# Macropadmod.net
KiCad netlist of a schematic drawn in Altium Designer
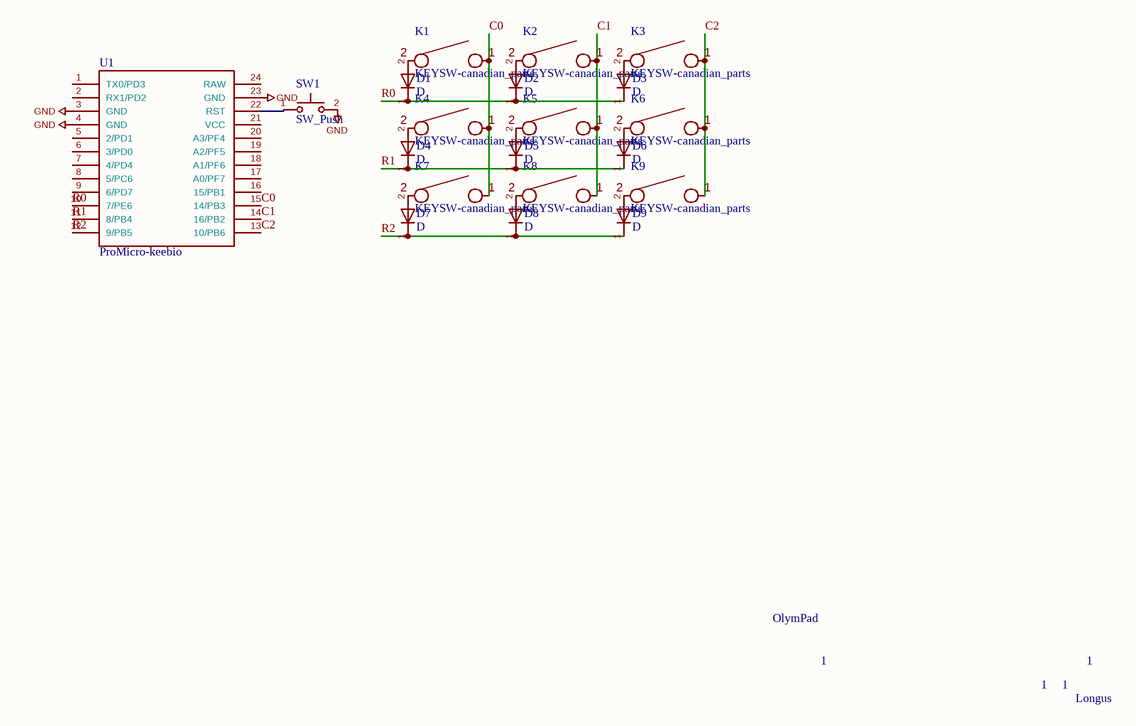
[diagram p0: Macropadmod.SchDoc]

(export (version "E")
  (design (tool "Eeschema 10.0.6"))
  (components
    (comp (ref "D1") (value "D") (footprint "Diode") (libsource (lib "Macropad") (part "D")))
    (comp (ref "D2") (value "D") (footprint "Diode") (libsource (lib "Macropad") (part "D")))
    (comp (ref "D3") (value "D") (footprint "Diode") (libsource (lib "Macropad") (part "D")))
    (comp (ref "D4") (value "D") (footprint "Diode") (libsource (lib "Macropad") (part "D")))
    (comp (ref "D5") (value "D") (footprint "Diode") (libsource (lib "Macropad") (part "D")))
    (comp (ref "D6") (value "D") (footprint "Diode") (libsource (lib "Macropad") (part "D")))
    (comp (ref "D7") (value "D") (footprint "Diode") (libsource (lib "Macropad") (part "D")))
    (comp (ref "D8") (value "D") (footprint "Diode") (libsource (lib "Macropad") (part "D")))
    (comp (ref "D9") (value "D") (footprint "Diode") (libsource (lib "Macropad") (part "D")))
    (comp (ref "K1")
      (value "KEYSW-canadian_parts")
      (footprint "Socket")
      (libsource (lib "Macropad") (part "KEYSW-canadian_parts"))
    )
    (comp (ref "K2")
      (value "KEYSW-canadian_parts")
      (footprint "Socket")
      (libsource (lib "Macropad") (part "KEYSW-canadian_parts"))
    )
    (comp (ref "K3")
      (value "KEYSW-canadian_parts")
      (footprint "Socket")
      (libsource (lib "Macropad") (part "KEYSW-canadian_parts"))
    )
    (comp (ref "K4")
      (value "KEYSW-canadian_parts")
      (footprint "Socket")
      (libsource (lib "Macropad") (part "KEYSW-canadian_parts"))
    )
    (comp (ref "K5")
      (value "KEYSW-canadian_parts")
      (footprint "Socket")
      (libsource (lib "Macropad") (part "KEYSW-canadian_parts"))
    )
    (comp (ref "K6")
      (value "KEYSW-canadian_parts")
      (footprint "Socket")
      (libsource (lib "Macropad") (part "KEYSW-canadian_parts"))
    )
    (comp (ref "K7")
      (value "KEYSW-canadian_parts")
      (footprint "Socket")
      (libsource (lib "Macropad") (part "KEYSW-canadian_parts"))
    )
    (comp (ref "K8")
      (value "KEYSW-canadian_parts")
      (footprint "Socket")
      (libsource (lib "Macropad") (part "KEYSW-canadian_parts"))
    )
    (comp (ref "K9")
      (value "KEYSW-canadian_parts")
      (footprint "Socket")
      (libsource (lib "Macropad") (part "KEYSW-canadian_parts"))
    )
    (comp (ref "SW1") (value "SW_Push") (footprint "Reset") (libsource (lib "Macropad") (part "SW_Push")))
    (comp (ref "U1")
      (value "ProMicro-keebio")
      (footprint "Pro-Micro")
      (libsource (lib "Macropad") (part "ProMicro-keebio"))
    )
  )
  (nets
    (net (code "1") (name "/C0") (class "Default")
      (node (ref "K1") (pin "1") (pinfunction "1_1") (pintype "passive"))
      (node (ref "K4") (pin "1") (pinfunction "1_1") (pintype "passive"))
      (node (ref "K7") (pin "1") (pinfunction "1_1") (pintype "passive"))
      (node (ref "U1") (pin "15") (pinfunction "14/PB3_15") (pintype "passive"))
    )
    (net (code "2") (name "/C1") (class "Default")
      (node (ref "K2") (pin "1") (pinfunction "1_1") (pintype "passive"))
      (node (ref "K5") (pin "1") (pinfunction "1_1") (pintype "passive"))
      (node (ref "K8") (pin "1") (pinfunction "1_1") (pintype "passive"))
      (node (ref "U1") (pin "14") (pinfunction "16/PB2_14") (pintype "passive"))
    )
    (net (code "3") (name "/C2") (class "Default")
      (node (ref "K3") (pin "1") (pinfunction "1_1") (pintype "passive"))
      (node (ref "K6") (pin "1") (pinfunction "1_1") (pintype "passive"))
      (node (ref "K9") (pin "1") (pinfunction "1_1") (pintype "passive"))
      (node (ref "U1") (pin "13") (pinfunction "10/PB6_13") (pintype "passive"))
    )
    (net (code "4") (name "/R0") (class "Default")
      (node (ref "D1") (pin "1") (pinfunction "K_1") (pintype "passive"))
      (node (ref "D2") (pin "1") (pinfunction "K_1") (pintype "passive"))
      (node (ref "D3") (pin "1") (pinfunction "K_1") (pintype "passive"))
      (node (ref "U1") (pin "10") (pinfunction "7/PE6_10") (pintype "passive"))
    )
    (net (code "5") (name "/R1") (class "Default")
      (node (ref "D4") (pin "1") (pinfunction "K_1") (pintype "passive"))
      (node (ref "D5") (pin "1") (pinfunction "K_1") (pintype "passive"))
      (node (ref "D6") (pin "1") (pinfunction "K_1") (pintype "passive"))
      (node (ref "U1") (pin "11") (pinfunction "8/PB4_11") (pintype "passive"))
    )
    (net (code "6") (name "/R2") (class "Default")
      (node (ref "D7") (pin "1") (pinfunction "K_1") (pintype "passive"))
      (node (ref "D8") (pin "1") (pinfunction "K_1") (pintype "passive"))
      (node (ref "D9") (pin "1") (pinfunction "K_1") (pintype "passive"))
      (node (ref "U1") (pin "12") (pinfunction "9/PB5_12") (pintype "passive"))
    )
    (net (code "7") (name "GND") (class "Default")
      (node (ref "SW1") (pin "2") (pinfunction "2_2") (pintype "passive"))
      (node (ref "U1") (pin "23") (pinfunction "GND_23") (pintype "passive"))
      (node (ref "U1") (pin "3") (pinfunction "GND_3") (pintype "passive"))
      (node (ref "U1") (pin "4") (pinfunction "GND_4") (pintype "passive"))
    )
    (net (code "8") (name "Net-(D1-A)") (class "Default")
      (node (ref "D1") (pin "2") (pinfunction "A_2") (pintype "passive"))
      (node (ref "K1") (pin "2") (pinfunction "2_2") (pintype "passive"))
    )
    (net (code "9") (name "Net-(D2-A)") (class "Default")
      (node (ref "D2") (pin "2") (pinfunction "A_2") (pintype "passive"))
      (node (ref "K2") (pin "2") (pinfunction "2_2") (pintype "passive"))
    )
    (net (code "10") (name "Net-(D3-A)") (class "Default")
      (node (ref "D3") (pin "2") (pinfunction "A_2") (pintype "passive"))
      (node (ref "K3") (pin "2") (pinfunction "2_2") (pintype "passive"))
    )
    (net (code "11") (name "Net-(D4-A)") (class "Default")
      (node (ref "D4") (pin "2") (pinfunction "A_2") (pintype "passive"))
      (node (ref "K4") (pin "2") (pinfunction "2_2") (pintype "passive"))
    )
    (net (code "12") (name "Net-(D5-A)") (class "Default")
      (node (ref "D5") (pin "2") (pinfunction "A_2") (pintype "passive"))
      (node (ref "K5") (pin "2") (pinfunction "2_2") (pintype "passive"))
    )
    (net (code "13") (name "Net-(D6-A)") (class "Default")
      (node (ref "D6") (pin "2") (pinfunction "A_2") (pintype "passive"))
      (node (ref "K6") (pin "2") (pinfunction "2_2") (pintype "passive"))
    )
    (net (code "14") (name "Net-(D7-A)") (class "Default")
      (node (ref "D7") (pin "2") (pinfunction "A_2") (pintype "passive"))
      (node (ref "K7") (pin "2") (pinfunction "2_2") (pintype "passive"))
    )
    (net (code "15") (name "Net-(D8-A)") (class "Default")
      (node (ref "D8") (pin "2") (pinfunction "A_2") (pintype "passive"))
      (node (ref "K8") (pin "2") (pinfunction "2_2") (pintype "passive"))
    )
    (net (code "16") (name "Net-(D9-A)") (class "Default")
      (node (ref "D9") (pin "2") (pinfunction "A_2") (pintype "passive"))
      (node (ref "K9") (pin "2") (pinfunction "2_2") (pintype "passive"))
    )
    (net (code "17") (name "Net-(U1-RST)") (class "Default")
      (node (ref "SW1") (pin "1") (pinfunction "1_1") (pintype "passive"))
      (node (ref "U1") (pin "22") (pinfunction "RST_22") (pintype "passive"))
    )
    (net (code "18") (name "unconnected-(U1-2{slash}PD1-Pad5)") (class "Default")
      (node (ref "U1") (pin "5") (pinfunction "2/PD1_5") (pintype "passive"))
    )
    (net (code "19") (name "unconnected-(U1-3{slash}PD0-Pad6)") (class "Default")
      (node (ref "U1") (pin "6") (pinfunction "3/PD0_6") (pintype "passive"))
    )
    (net (code "20") (name "unconnected-(U1-4{slash}PD4-Pad7)") (class "Default")
      (node (ref "U1") (pin "7") (pinfunction "4/PD4_7") (pintype "passive"))
    )
    (net (code "21") (name "unconnected-(U1-5{slash}PC6-Pad8)") (class "Default")
      (node (ref "U1") (pin "8") (pinfunction "5/PC6_8") (pintype "passive"))
    )
    (net (code "22") (name "unconnected-(U1-6{slash}PD7-Pad9)") (class "Default")
      (node (ref "U1") (pin "9") (pinfunction "6/PD7_9") (pintype "passive"))
    )
    (net (code "23") (name "unconnected-(U1-15{slash}PB1-Pad16)") (class "Default")
      (node (ref "U1") (pin "16") (pinfunction "15/PB1_16") (pintype "passive"))
    )
    (net (code "24") (name "unconnected-(U1-A0{slash}PF7-Pad17)") (class "Default")
      (node (ref "U1") (pin "17") (pinfunction "A0/PF7_17") (pintype "passive"))
    )
    (net (code "25") (name "unconnected-(U1-A1{slash}PF6-Pad18)") (class "Default")
      (node (ref "U1") (pin "18") (pinfunction "A1/PF6_18") (pintype "passive"))
    )
    (net (code "26") (name "unconnected-(U1-A2{slash}PF5-Pad19)") (class "Default")
      (node (ref "U1") (pin "19") (pinfunction "A2/PF5_19") (pintype "passive"))
    )
    (net (code "27") (name "unconnected-(U1-A3{slash}PF4-Pad20)") (class "Default")
      (node (ref "U1") (pin "20") (pinfunction "A3/PF4_20") (pintype "passive"))
    )
    (net (code "28") (name "unconnected-(U1-RAW-Pad24)") (class "Default")
      (node (ref "U1") (pin "24") (pinfunction "RAW_24") (pintype "passive"))
    )
    (net (code "29") (name "unconnected-(U1-RX1{slash}PD2-Pad2)") (class "Default")
      (node (ref "U1") (pin "2") (pinfunction "RX1/PD2_2") (pintype "passive"))
    )
    (net (code "30") (name "unconnected-(U1-TX0{slash}PD3-Pad1)") (class "Default")
      (node (ref "U1") (pin "1") (pinfunction "TX0/PD3_1") (pintype "passive"))
    )
    (net (code "31") (name "unconnected-(U1-VCC-Pad21)") (class "Default")
      (node (ref "U1") (pin "21") (pinfunction "VCC_21") (pintype "passive"))
    )
  )
)
